# Mainboard.net
KiCad netlist of a schematic drawn in Altium Designer
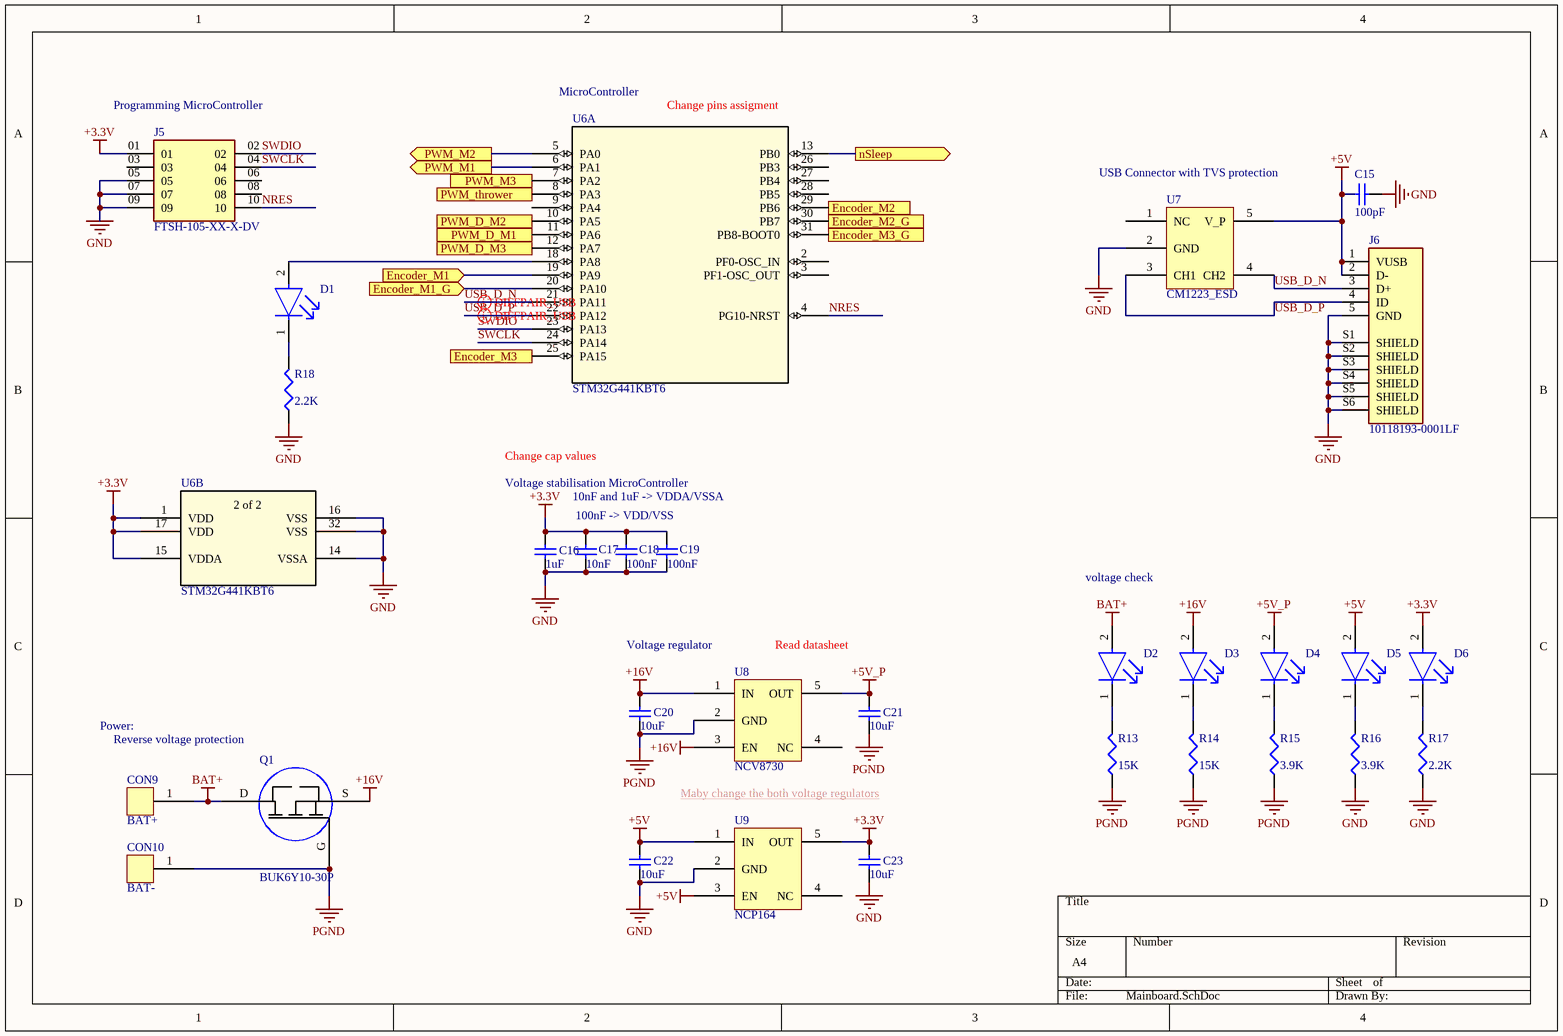
[diagram p0: Mainboard.SchDoc]

(export (version "E")
  (design (tool "Eeschema 10.0.6"))
  (components
    (comp (ref "C15")
      (value "100pF")
      (footprint "1608[0603]")
      (description "Capacitor (Semiconductor SIM Model)")
      (fields (field (name "Comment") "Cap Semi") (field (name "PUBLISHER") "Altium Limited"))
      (libsource (lib "Miscellaneous Devices") (part "Cap Semi"))
    )
    (comp (ref "C16")
      (value "1uF")
      (footprint "1608[0603]")
      (description "Capacitor (Semiconductor SIM Model)")
      (fields (field (name "Comment") "Cap Semi") (field (name "PUBLISHER") "Altium Limited"))
      (libsource (lib "Miscellaneous Devices") (part "Cap Semi"))
    )
    (comp (ref "C17")
      (value "10nF")
      (footprint "1608[0603]")
      (description "Capacitor (Semiconductor SIM Model)")
      (fields (field (name "Comment") "Cap Semi") (field (name "PUBLISHER") "Altium Limited"))
      (libsource (lib "Miscellaneous Devices") (part "Cap Semi"))
    )
    (comp (ref "C18")
      (value "100nF")
      (footprint "1608[0603]")
      (description "Capacitor (Semiconductor SIM Model)")
      (fields (field (name "Comment") "Cap Semi") (field (name "PUBLISHER") "Altium Limited"))
      (libsource (lib "Miscellaneous Devices") (part "Cap Semi"))
    )
    (comp (ref "C19")
      (value "100nF")
      (footprint "1608[0603]")
      (description "Capacitor (Semiconductor SIM Model)")
      (fields (field (name "Comment") "Cap Semi") (field (name "PUBLISHER") "Altium Limited"))
      (libsource (lib "Miscellaneous Devices") (part "Cap Semi"))
    )
    (comp (ref "C20")
      (value "10uF")
      (footprint "C1206")
      (description "Capacitor (Semiconductor SIM Model)")
      (fields (field (name "Comment") "Cap Semi") (field (name "PUBLISHER") "Altium Limited"))
      (libsource (lib "Miscellaneous Devices") (part "Cap Semi"))
    )
    (comp (ref "C21")
      (value "10uF")
      (footprint "C1206")
      (description "Capacitor (Semiconductor SIM Model)")
      (fields (field (name "Comment") "Cap Semi") (field (name "PUBLISHER") "Altium Limited"))
      (libsource (lib "Miscellaneous Devices") (part "Cap Semi"))
    )
    (comp (ref "C22")
      (value "10uF")
      (footprint "C1206")
      (description "Capacitor (Semiconductor SIM Model)")
      (fields (field (name "Comment") "Cap Semi") (field (name "PUBLISHER") "Altium Limited"))
      (libsource (lib "Miscellaneous Devices") (part "Cap Semi"))
    )
    (comp (ref "C23")
      (value "10uF")
      (footprint "C1206")
      (description "Capacitor (Semiconductor SIM Model)")
      (fields (field (name "Comment") "Cap Semi") (field (name "PUBLISHER") "Altium Limited"))
      (libsource (lib "Miscellaneous Devices") (part "Cap Semi"))
    )
    (comp (ref "CON9")
      (value "BAT+")
      (footprint "con_soldering")
      (libsource (lib "con_soldering") (part "Con_soldering"))
    )
    (comp (ref "CON10")
      (value "BAT-")
      (footprint "con_soldering")
      (libsource (lib "con_soldering") (part "Con_soldering"))
    )
    (comp (ref "D1")
      (value "LTST-C190GKT")
      (footprint "FP-LTST-C190GKT-MFG")
      (description "LED GREEN CLEAR CHIP SMD")
      (fields (field (name "VOLTAGE") "2V"))
      (libsource (lib "Altium Content Vault") (part "8706943c75ba83719d021d2fdc84c58"))
    )
    (comp (ref "D2")
      (value "LTST-C190GKT")
      (footprint "FP-LTST-C190GKT-MFG")
      (description "LED GREEN CLEAR CHIP SMD")
      (fields (field (name "VOLTAGE") "2V"))
      (libsource (lib "Altium Content Vault") (part "8706943c75ba83719d021d2fdc84c58"))
    )
    (comp (ref "D3")
      (value "LTST-C190GKT")
      (footprint "FP-LTST-C190GKT-MFG")
      (description "LED GREEN CLEAR CHIP SMD")
      (fields (field (name "VOLTAGE") "2V"))
      (libsource (lib "Altium Content Vault") (part "8706943c75ba83719d021d2fdc84c58"))
    )
    (comp (ref "D4")
      (value "LTST-C190GKT")
      (footprint "FP-LTST-C190GKT-MFG")
      (description "LED GREEN CLEAR CHIP SMD")
      (fields (field (name "VOLTAGE") "2V"))
      (libsource (lib "Altium Content Vault") (part "8706943c75ba83719d021d2fdc84c58"))
    )
    (comp (ref "D5")
      (value "LTST-C190GKT")
      (footprint "FP-LTST-C190GKT-MFG")
      (description "LED GREEN CLEAR CHIP SMD")
      (fields (field (name "VOLTAGE") "2V"))
      (libsource (lib "Altium Content Vault") (part "8706943c75ba83719d021d2fdc84c58"))
    )
    (comp (ref "D6")
      (value "LTST-C190GKT")
      (footprint "FP-LTST-C190GKT-MFG")
      (description "LED GREEN CLEAR CHIP SMD")
      (fields (field (name "VOLTAGE") "2V"))
      (libsource (lib "Altium Content Vault") (part "8706943c75ba83719d021d2fdc84c58"))
    )
    (comp (ref "J5")
      (value "FTSH-105-XX-X-DV")
      (footprint "SAMTEC_FTSH-105-XX-X-DV")
      (description "Connector Header Surface Mount 10 position 0.050\" (1.27mm)")
      (libsource (lib "FTSH-105-XX-X-DV") (part "FTSH-105-XX-X-DV"))
    )
    (comp (ref "J6")
      (value "10118193-0001LF")
      (footprint "FCI_10118193-0001LF")
      (description "USB - micro B USB 2.0 Receptacle Connector 5 Position Surface Mount, Right Angle; Through Hole")
      (fields (field (name "MF") "Amphenol ICC"))
      (libsource (lib "SnapEDAsch") (part "10118193-0001LF"))
    )
    (comp (ref "Q1")
      (value "BUK6Y10-30P")
      (footprint "TRANS_PSMN5R5-60YS,115")
      (libsource (lib "BUK6Y10-30P") (part "BUK6Y10-30P"))
    )
    (comp (ref "R13")
      (value "15K")
      (footprint "J1-0603")
      (description "Resistor")
      (fields (field (name "Comment") "Res3") (field (name "PUBLISHER") "Altium Limited"))
      (libsource (lib "Miscellaneous Devices") (part "Res3"))
    )
    (comp (ref "R14")
      (value "15K")
      (footprint "J1-0603")
      (description "Resistor")
      (fields (field (name "Comment") "Res3") (field (name "PUBLISHER") "Altium Limited"))
      (libsource (lib "Miscellaneous Devices") (part "Res3"))
    )
    (comp (ref "R15")
      (value "3.9K")
      (footprint "J1-0603")
      (description "Resistor")
      (fields (field (name "Comment") "Res3") (field (name "PUBLISHER") "Altium Limited"))
      (libsource (lib "Miscellaneous Devices") (part "Res3"))
    )
    (comp (ref "R16")
      (value "3.9K")
      (footprint "J1-0603")
      (description "Resistor")
      (fields (field (name "Comment") "Res3") (field (name "PUBLISHER") "Altium Limited"))
      (libsource (lib "Miscellaneous Devices") (part "Res3"))
    )
    (comp (ref "R17")
      (value "2.2K")
      (footprint "J1-0603")
      (description "Resistor")
      (fields (field (name "Comment") "Res3") (field (name "PUBLISHER") "Altium Limited"))
      (libsource (lib "Miscellaneous Devices") (part "Res3"))
    )
    (comp (ref "R18")
      (value "2.2K")
      (footprint "J1-0603")
      (description "Resistor")
      (fields (field (name "Comment") "Res3") (field (name "PUBLISHER") "Altium Limited"))
      (libsource (lib "Miscellaneous Devices") (part "Res3"))
    )
    (comp (ref "U6")
      (value "STM32G441KBT6")
      (footprint "LQFP-32")
      (description "No Description Available")
      (fields (field (name "COPYRIGHT") "Copyright (C) 2021 Ultra Librarian. All rights reserved."))
      (libsource (lib "STM32G441KBT6") (part "STM32G441KBT6"))
    )
    (comp (ref "U7")
      (value "CM1223_ESD")
      (footprint "CM1223_ESD")
      (libsource (lib "CM1223_ESD") (part "CM1223_ESD"))
    )
    (comp (ref "U8")
      (value "NCV8730")
      (footprint "NCP164CSN330T1G_Voltage_regulator")
      (libsource (lib "NCV8730") (part "NCV8730"))
    )
    (comp (ref "U9")
      (value "NCP164")
      (footprint "NCP164CSN330T1G_Voltage_regulator")
      (libsource (lib "NCP164_voltage_5to3V3") (part "NCP164"))
    )
  )
  (nets
    (net (code "1") (name "+3.3V") (class "Default")
      (node (ref "C16") (pin "2") (pinfunction "2_2") (pintype "passive"))
      (node (ref "C17") (pin "2") (pinfunction "2_2") (pintype "passive"))
      (node (ref "C18") (pin "2") (pinfunction "2_2") (pintype "passive"))
      (node (ref "C19") (pin "2") (pinfunction "2_2") (pintype "passive"))
      (node (ref "C23") (pin "2") (pinfunction "2_2") (pintype "passive"))
      (node (ref "D6") (pin "2") (pinfunction "A_2") (pintype "passive"))
      (node (ref "J5") (pin "01") (pinfunction "01_01") (pintype "passive"))
      (node (ref "U6") (pin "1") (pinfunction "VDD_1") (pintype "power_in"))
      (node (ref "U6") (pin "15") (pinfunction "VDDA_15") (pintype "power_in"))
      (node (ref "U6") (pin "17") (pinfunction "VDD_17") (pintype "power_in"))
      (node (ref "U9") (pin "5") (pinfunction "OUT_5") (pintype "passive"))
    )
    (net (code "2") (name "+5V") (class "Default")
      (node (ref "C15") (pin "2") (pinfunction "2_2") (pintype "passive"))
      (node (ref "C22") (pin "2") (pinfunction "2_2") (pintype "passive"))
      (node (ref "D5") (pin "2") (pinfunction "A_2") (pintype "passive"))
      (node (ref "J6") (pin "1") (pinfunction "VUSB_1") (pintype "passive"))
      (node (ref "J6") (pin "2") (pinfunction "D-_2") (pintype "passive"))
      (node (ref "U7") (pin "5") (pinfunction "V_P_5") (pintype "passive"))
      (node (ref "U9") (pin "1") (pinfunction "IN_1") (pintype "passive"))
      (node (ref "U9") (pin "3") (pinfunction "EN_3") (pintype "passive"))
    )
    (net (code "3") (name "+5V_P") (class "Default")
      (node (ref "C21") (pin "2") (pinfunction "2_2") (pintype "passive"))
      (node (ref "D4") (pin "2") (pinfunction "A_2") (pintype "passive"))
      (node (ref "U8") (pin "5") (pinfunction "OUT_5") (pintype "passive"))
    )
    (net (code "4") (name "+16V") (class "Default")
      (node (ref "C20") (pin "2") (pinfunction "2_2") (pintype "passive"))
      (node (ref "D3") (pin "2") (pinfunction "A_2") (pintype "passive"))
      (node (ref "Q1") (pin "S") (pinfunction "S_S") (pintype "passive"))
      (node (ref "U8") (pin "1") (pinfunction "IN_1") (pintype "passive"))
      (node (ref "U8") (pin "3") (pinfunction "EN_3") (pintype "passive"))
    )
    (net (code "5") (name "/Encoder_M1") (class "Default")
      (node (ref "U6") (pin "19") (pinfunction "PA9_19") (pintype "bidirectional"))
    )
    (net (code "6") (name "/Encoder_M1_G") (class "Default")
      (node (ref "U6") (pin "20") (pinfunction "PA10_20") (pintype "bidirectional"))
    )
    (net (code "7") (name "/Encoder_M2") (class "Default")
      (node (ref "U6") (pin "29") (pinfunction "PB6_29") (pintype "bidirectional"))
    )
    (net (code "8") (name "/Encoder_M2_G") (class "Default")
      (node (ref "U6") (pin "30") (pinfunction "PB7_30") (pintype "bidirectional"))
    )
    (net (code "9") (name "/Encoder_M3") (class "Default")
      (node (ref "U6") (pin "25") (pinfunction "PA15_25") (pintype "bidirectional"))
    )
    (net (code "10") (name "/Encoder_M3_G") (class "Default")
      (node (ref "U6") (pin "31") (pinfunction "PB8-BOOT0_31") (pintype "bidirectional"))
    )
    (net (code "11") (name "/NRES") (class "Default")
      (node (ref "J5") (pin "10") (pinfunction "10_10") (pintype "passive"))
      (node (ref "U6") (pin "4") (pinfunction "PG10-NRST_4") (pintype "bidirectional"))
    )
    (net (code "12") (name "/PWM_D_M1") (class "Default")
      (node (ref "U6") (pin "11") (pinfunction "PA6_11") (pintype "bidirectional"))
    )
    (net (code "13") (name "/PWM_D_M2") (class "Default")
      (node (ref "U6") (pin "10") (pinfunction "PA5_10") (pintype "bidirectional"))
    )
    (net (code "14") (name "/PWM_D_M3") (class "Default")
      (node (ref "U6") (pin "12") (pinfunction "PA7_12") (pintype "bidirectional"))
    )
    (net (code "15") (name "/PWM_M1") (class "Default")
      (node (ref "U6") (pin "6") (pinfunction "PA1_6") (pintype "bidirectional"))
    )
    (net (code "16") (name "/PWM_M2") (class "Default")
      (node (ref "U6") (pin "5") (pinfunction "PA0_5") (pintype "bidirectional"))
    )
    (net (code "17") (name "/PWM_M3") (class "Default")
      (node (ref "U6") (pin "7") (pinfunction "PA2_7") (pintype "bidirectional"))
    )
    (net (code "18") (name "/PWM_thrower") (class "Default")
      (node (ref "U6") (pin "8") (pinfunction "PA3_8") (pintype "bidirectional"))
    )
    (net (code "19") (name "/SWCLK") (class "Default")
      (node (ref "J5") (pin "04") (pinfunction "04_04") (pintype "passive"))
      (node (ref "U6") (pin "24") (pinfunction "PA14_24") (pintype "bidirectional"))
    )
    (net (code "20") (name "/SWDIO") (class "Default")
      (node (ref "J5") (pin "02") (pinfunction "02_02") (pintype "passive"))
      (node (ref "U6") (pin "23") (pinfunction "PA13_23") (pintype "bidirectional"))
    )
    (net (code "21") (name "/USB_D_N") (class "Default")
      (node (ref "J6") (pin "3") (pinfunction "D+_3") (pintype "passive"))
      (node (ref "U6") (pin "21") (pinfunction "PA11_21") (pintype "bidirectional"))
      (node (ref "U7") (pin "4") (pinfunction "CH2_4") (pintype "passive"))
    )
    (net (code "22") (name "/USB_D_P") (class "Default")
      (node (ref "J6") (pin "4") (pinfunction "ID_4") (pintype "passive"))
      (node (ref "U6") (pin "22") (pinfunction "PA12_22") (pintype "bidirectional"))
      (node (ref "U7") (pin "3") (pinfunction "CH1_3") (pintype "passive"))
    )
    (net (code "23") (name "/nSleep") (class "Default")
      (node (ref "U6") (pin "13") (pinfunction "PB0_13") (pintype "bidirectional"))
    )
    (net (code "24") (name "BAT+") (class "Default")
      (node (ref "CON9") (pin "1") (pintype "passive"))
      (node (ref "D2") (pin "2") (pinfunction "A_2") (pintype "passive"))
      (node (ref "Q1") (pin "D") (pinfunction "D_D") (pintype "passive"))
    )
    (net (code "25") (name "GND") (class "Default")
      (node (ref "C15") (pin "1") (pinfunction "1_1") (pintype "passive"))
      (node (ref "C16") (pin "1") (pinfunction "1_1") (pintype "passive"))
      (node (ref "C17") (pin "1") (pinfunction "1_1") (pintype "passive"))
      (node (ref "C18") (pin "1") (pinfunction "1_1") (pintype "passive"))
      (node (ref "C19") (pin "1") (pinfunction "1_1") (pintype "passive"))
      (node (ref "C22") (pin "1") (pinfunction "1_1") (pintype "passive"))
      (node (ref "C23") (pin "1") (pinfunction "1_1") (pintype "passive"))
      (node (ref "J5") (pin "05") (pinfunction "05_05") (pintype "passive"))
      (node (ref "J5") (pin "07") (pinfunction "07_07") (pintype "passive"))
      (node (ref "J5") (pin "09") (pinfunction "09_09") (pintype "passive"))
      (node (ref "J6") (pin "5") (pinfunction "GND_5") (pintype "passive"))
      (node (ref "J6") (pin "S1") (pinfunction "SHIELD_S1") (pintype "passive"))
      (node (ref "J6") (pin "S2") (pinfunction "SHIELD_S2") (pintype "passive"))
      (node (ref "J6") (pin "S3") (pinfunction "SHIELD_S3") (pintype "passive"))
      (node (ref "J6") (pin "S4") (pinfunction "SHIELD_S4") (pintype "passive"))
      (node (ref "J6") (pin "S5") (pinfunction "SHIELD_S5") (pintype "passive"))
      (node (ref "J6") (pin "S6") (pinfunction "SHIELD_S6") (pintype "passive"))
      (node (ref "R16") (pin "1") (pinfunction "1_1") (pintype "passive"))
      (node (ref "R17") (pin "1") (pinfunction "1_1") (pintype "passive"))
      (node (ref "R18") (pin "1") (pinfunction "1_1") (pintype "passive"))
      (node (ref "U6") (pin "14") (pinfunction "VSSA_14") (pintype "power_in"))
      (node (ref "U6") (pin "16") (pinfunction "VSS_16") (pintype "power_in"))
      (node (ref "U6") (pin "32") (pinfunction "VSS_32") (pintype "power_in"))
      (node (ref "U7") (pin "2") (pinfunction "GND_2") (pintype "passive"))
      (node (ref "U9") (pin "2") (pinfunction "GND_2") (pintype "passive"))
    )
    (net (code "26") (name "Net-(D1-A)") (class "Default")
      (node (ref "D1") (pin "2") (pinfunction "A_2") (pintype "passive"))
      (node (ref "U6") (pin "18") (pinfunction "PA8_18") (pintype "bidirectional"))
    )
    (net (code "27") (name "Net-(D1-C)") (class "Default")
      (node (ref "D1") (pin "1") (pinfunction "C_1") (pintype "passive"))
      (node (ref "R18") (pin "2") (pinfunction "2_2") (pintype "passive"))
    )
    (net (code "28") (name "Net-(D2-C)") (class "Default")
      (node (ref "D2") (pin "1") (pinfunction "C_1") (pintype "passive"))
      (node (ref "R13") (pin "2") (pinfunction "2_2") (pintype "passive"))
    )
    (net (code "29") (name "Net-(D3-C)") (class "Default")
      (node (ref "D3") (pin "1") (pinfunction "C_1") (pintype "passive"))
      (node (ref "R14") (pin "2") (pinfunction "2_2") (pintype "passive"))
    )
    (net (code "30") (name "Net-(D4-C)") (class "Default")
      (node (ref "D4") (pin "1") (pinfunction "C_1") (pintype "passive"))
      (node (ref "R15") (pin "2") (pinfunction "2_2") (pintype "passive"))
    )
    (net (code "31") (name "Net-(D5-C)") (class "Default")
      (node (ref "D5") (pin "1") (pinfunction "C_1") (pintype "passive"))
      (node (ref "R16") (pin "2") (pinfunction "2_2") (pintype "passive"))
    )
    (net (code "32") (name "Net-(D6-C)") (class "Default")
      (node (ref "D6") (pin "1") (pinfunction "C_1") (pintype "passive"))
      (node (ref "R17") (pin "2") (pinfunction "2_2") (pintype "passive"))
    )
    (net (code "33") (name "PGND") (class "Default")
      (node (ref "C20") (pin "1") (pinfunction "1_1") (pintype "passive"))
      (node (ref "C21") (pin "1") (pinfunction "1_1") (pintype "passive"))
      (node (ref "CON10") (pin "1") (pintype "passive"))
      (node (ref "Q1") (pin "G") (pinfunction "G_G") (pintype "passive"))
      (node (ref "R13") (pin "1") (pinfunction "1_1") (pintype "passive"))
      (node (ref "R14") (pin "1") (pinfunction "1_1") (pintype "passive"))
      (node (ref "R15") (pin "1") (pinfunction "1_1") (pintype "passive"))
      (node (ref "U8") (pin "2") (pinfunction "GND_2") (pintype "passive"))
    )
    (net (code "34") (name "unconnected-(J5-Pad03)") (class "Default")
      (node (ref "J5") (pin "03") (pinfunction "03_03") (pintype "passive"))
    )
    (net (code "35") (name "unconnected-(J5-Pad06)") (class "Default")
      (node (ref "J5") (pin "06") (pinfunction "06_06") (pintype "passive"))
    )
    (net (code "36") (name "unconnected-(J5-Pad08)") (class "Default")
      (node (ref "J5") (pin "08") (pinfunction "08_08") (pintype "passive"))
    )
    (net (code "37") (name "unconnected-(U6A-PA4-Pad9)") (class "Default")
      (node (ref "U6") (pin "9") (pinfunction "PA4_9") (pintype "bidirectional"))
    )
    (net (code "38") (name "unconnected-(U6A-PB3-Pad26)") (class "Default")
      (node (ref "U6") (pin "26") (pinfunction "PB3_26") (pintype "bidirectional"))
    )
    (net (code "39") (name "unconnected-(U6A-PB4-Pad27)") (class "Default")
      (node (ref "U6") (pin "27") (pinfunction "PB4_27") (pintype "bidirectional"))
    )
    (net (code "40") (name "unconnected-(U6A-PB5-Pad28)") (class "Default")
      (node (ref "U6") (pin "28") (pinfunction "PB5_28") (pintype "bidirectional"))
    )
    (net (code "41") (name "unconnected-(U6A-PF0-OSC_IN-Pad2)") (class "Default")
      (node (ref "U6") (pin "2") (pinfunction "PF0-OSC_IN_2") (pintype "bidirectional"))
    )
    (net (code "42") (name "unconnected-(U6A-PF1-OSC_OUT-Pad3)") (class "Default")
      (node (ref "U6") (pin "3") (pinfunction "PF1-OSC_OUT_3") (pintype "bidirectional"))
    )
    (net (code "43") (name "unconnected-(U7-NC-Pad1)") (class "Default")
      (node (ref "U7") (pin "1") (pinfunction "NC_1") (pintype "passive"))
    )
    (net (code "44") (name "unconnected-(U8-NC-Pad4)") (class "Default")
      (node (ref "U8") (pin "4") (pinfunction "NC_4") (pintype "passive"))
    )
    (net (code "45") (name "unconnected-(U9-NC-Pad4)") (class "Default")
      (node (ref "U9") (pin "4") (pinfunction "NC_4") (pintype "passive"))
    )
  )
)
